# MP2225.net
KiCad netlist of a schematic drawn in Altium Designer
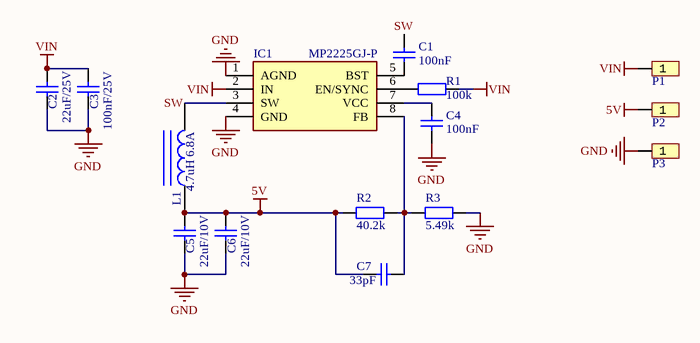
[diagram p0: MP2225.SchDoc]

(export (version "E")
  (design (tool "Eeschema 10.0.6"))
  (components
    (comp (ref "C1")
      (value "100nF")
      (footprint "CAP-0603")
      (description "贴片电容")
      (libsource (lib "Power_Lib_Altium") (part "CAP"))
    )
    (comp (ref "C2")
      (value "22uF/25V")
      (footprint "CAP-0603")
      (description "贴片电容")
      (libsource (lib "Power_Lib_Altium") (part "CAP"))
    )
    (comp (ref "C3")
      (value "100nF/25V")
      (footprint "CAP-0603")
      (description "贴片电容")
      (libsource (lib "Power_Lib_Altium") (part "CAP"))
    )
    (comp (ref "C4")
      (value "100nF")
      (footprint "CAP-0603")
      (description "贴片电容")
      (libsource (lib "Power_Lib_Altium") (part "CAP"))
    )
    (comp (ref "C5")
      (value "22uF/10V")
      (footprint "CAP-0603")
      (description "贴片电容")
      (libsource (lib "Power_Lib_Altium") (part "CAP"))
    )
    (comp (ref "C6")
      (value "22uF/10V")
      (footprint "CAP-0603")
      (description "贴片电容")
      (libsource (lib "Power_Lib_Altium") (part "CAP"))
    )
    (comp (ref "C7")
      (value "33pF")
      (footprint "CAP-0603")
      (description "贴片电容")
      (libsource (lib "Power_Lib_Altium") (part "CAP"))
    )
    (comp (ref "IC1")
      (value "MP2225GJ-P")
      (footprint "TSOT-23-8")
      (description "Switching Voltage Regulators HighEfficiency5A 18V Sync Step Down Conv")
      (fields (field (name "MOUSER PART NUMBER") "946-MP2225GJ-P"))
      (libsource (lib "Power_Lib_Altium") (part "MP2225GJ-P"))
    )
    (comp (ref "L1")
      (value "4.7uH 6.8A")
      (footprint "XAL6060-103MEB")
      (description "电感")
      (libsource (lib "Power_Lib_Altium") (part "INDUCTOR"))
    )
    (comp (ref "P1")
      (value "HDR1x2_2.54")
      (footprint "HDR1X1_2.54")
      (description "Header")
      (libsource (lib "Power_Lib_Altium") (part "HDR1x1_2.54"))
    )
    (comp (ref "P2")
      (value "HDR1x2_2.54")
      (footprint "HDR1X1_2.54")
      (description "Header")
      (libsource (lib "Power_Lib_Altium") (part "HDR1x1_2.54"))
    )
    (comp (ref "P3")
      (value "HDR1x2_2.54")
      (footprint "HDR1X1_2.54")
      (description "Header")
      (libsource (lib "Power_Lib_Altium") (part "HDR1x1_2.54"))
    )
    (comp (ref "R1")
      (value "100k")
      (footprint "R-0603")
      (description "贴片电阻")
      (libsource (lib "Power_Lib_Altium") (part "RES"))
    )
    (comp (ref "R2")
      (value "40.2k")
      (footprint "R-0603")
      (description "贴片电阻")
      (libsource (lib "Power_Lib_Altium") (part "RES"))
    )
    (comp (ref "R3")
      (value "5.49k")
      (footprint "R-0603")
      (description "贴片电阻")
      (libsource (lib "Power_Lib_Altium") (part "RES"))
    )
  )
  (nets
    (net (code "1") (name "/SW") (class "Default")
      (node (ref "C1") (pin "1") (pinfunction "1_1") (pintype "passive"))
      (node (ref "IC1") (pin "3") (pinfunction "SW_3") (pintype "passive"))
      (node (ref "L1") (pin "2") (pinfunction "2_2") (pintype "passive"))
    )
    (net (code "2") (name "5V") (class "Default")
      (node (ref "C5") (pin "2") (pinfunction "2_2") (pintype "passive"))
      (node (ref "C6") (pin "2") (pinfunction "2_2") (pintype "passive"))
      (node (ref "C7") (pin "2") (pinfunction "2_2") (pintype "passive"))
      (node (ref "L1") (pin "1") (pinfunction "1_1") (pintype "passive"))
      (node (ref "P2") (pin "1") (pinfunction "1_1") (pintype "passive"))
      (node (ref "R2") (pin "2") (pinfunction "2_2") (pintype "passive"))
    )
    (net (code "3") (name "GND") (class "Default")
      (node (ref "C2") (pin "1") (pinfunction "1_1") (pintype "passive"))
      (node (ref "C3") (pin "1") (pinfunction "1_1") (pintype "passive"))
      (node (ref "C4") (pin "1") (pinfunction "1_1") (pintype "passive"))
      (node (ref "C5") (pin "1") (pinfunction "1_1") (pintype "passive"))
      (node (ref "C6") (pin "1") (pinfunction "1_1") (pintype "passive"))
      (node (ref "IC1") (pin "1") (pinfunction "AGND_1") (pintype "passive"))
      (node (ref "IC1") (pin "4") (pinfunction "GND_4") (pintype "passive"))
      (node (ref "P3") (pin "1") (pinfunction "1_1") (pintype "passive"))
      (node (ref "R3") (pin "1") (pinfunction "1_1") (pintype "passive"))
    )
    (net (code "4") (name "Net-(IC1-BST)") (class "Default")
      (node (ref "C1") (pin "2") (pinfunction "2_2") (pintype "passive"))
      (node (ref "IC1") (pin "5") (pinfunction "BST_5") (pintype "passive"))
    )
    (net (code "5") (name "Net-(IC1-EN{slash}SYNC)") (class "Default")
      (node (ref "IC1") (pin "6") (pinfunction "EN/SYNC_6") (pintype "passive"))
      (node (ref "R1") (pin "2") (pinfunction "2_2") (pintype "passive"))
    )
    (net (code "6") (name "Net-(IC1-FB)") (class "Default")
      (node (ref "C7") (pin "1") (pinfunction "1_1") (pintype "passive"))
      (node (ref "IC1") (pin "8") (pinfunction "FB_8") (pintype "passive"))
      (node (ref "R2") (pin "1") (pinfunction "1_1") (pintype "passive"))
      (node (ref "R3") (pin "2") (pinfunction "2_2") (pintype "passive"))
    )
    (net (code "7") (name "Net-(IC1-VCC)") (class "Default")
      (node (ref "C4") (pin "2") (pinfunction "2_2") (pintype "passive"))
      (node (ref "IC1") (pin "7") (pinfunction "VCC_7") (pintype "passive"))
    )
    (net (code "8") (name "VIN") (class "Default")
      (node (ref "C2") (pin "2") (pinfunction "2_2") (pintype "passive"))
      (node (ref "C3") (pin "2") (pinfunction "2_2") (pintype "passive"))
      (node (ref "IC1") (pin "2") (pinfunction "IN_2") (pintype "passive"))
      (node (ref "P1") (pin "1") (pinfunction "1_1") (pintype "passive"))
      (node (ref "R1") (pin "1") (pinfunction "1_1") (pintype "passive"))
    )
  )
)
